# 468323_001_LED_DRV_ISO_2.net
KiCad netlist of a schematic drawn in Altium Designer
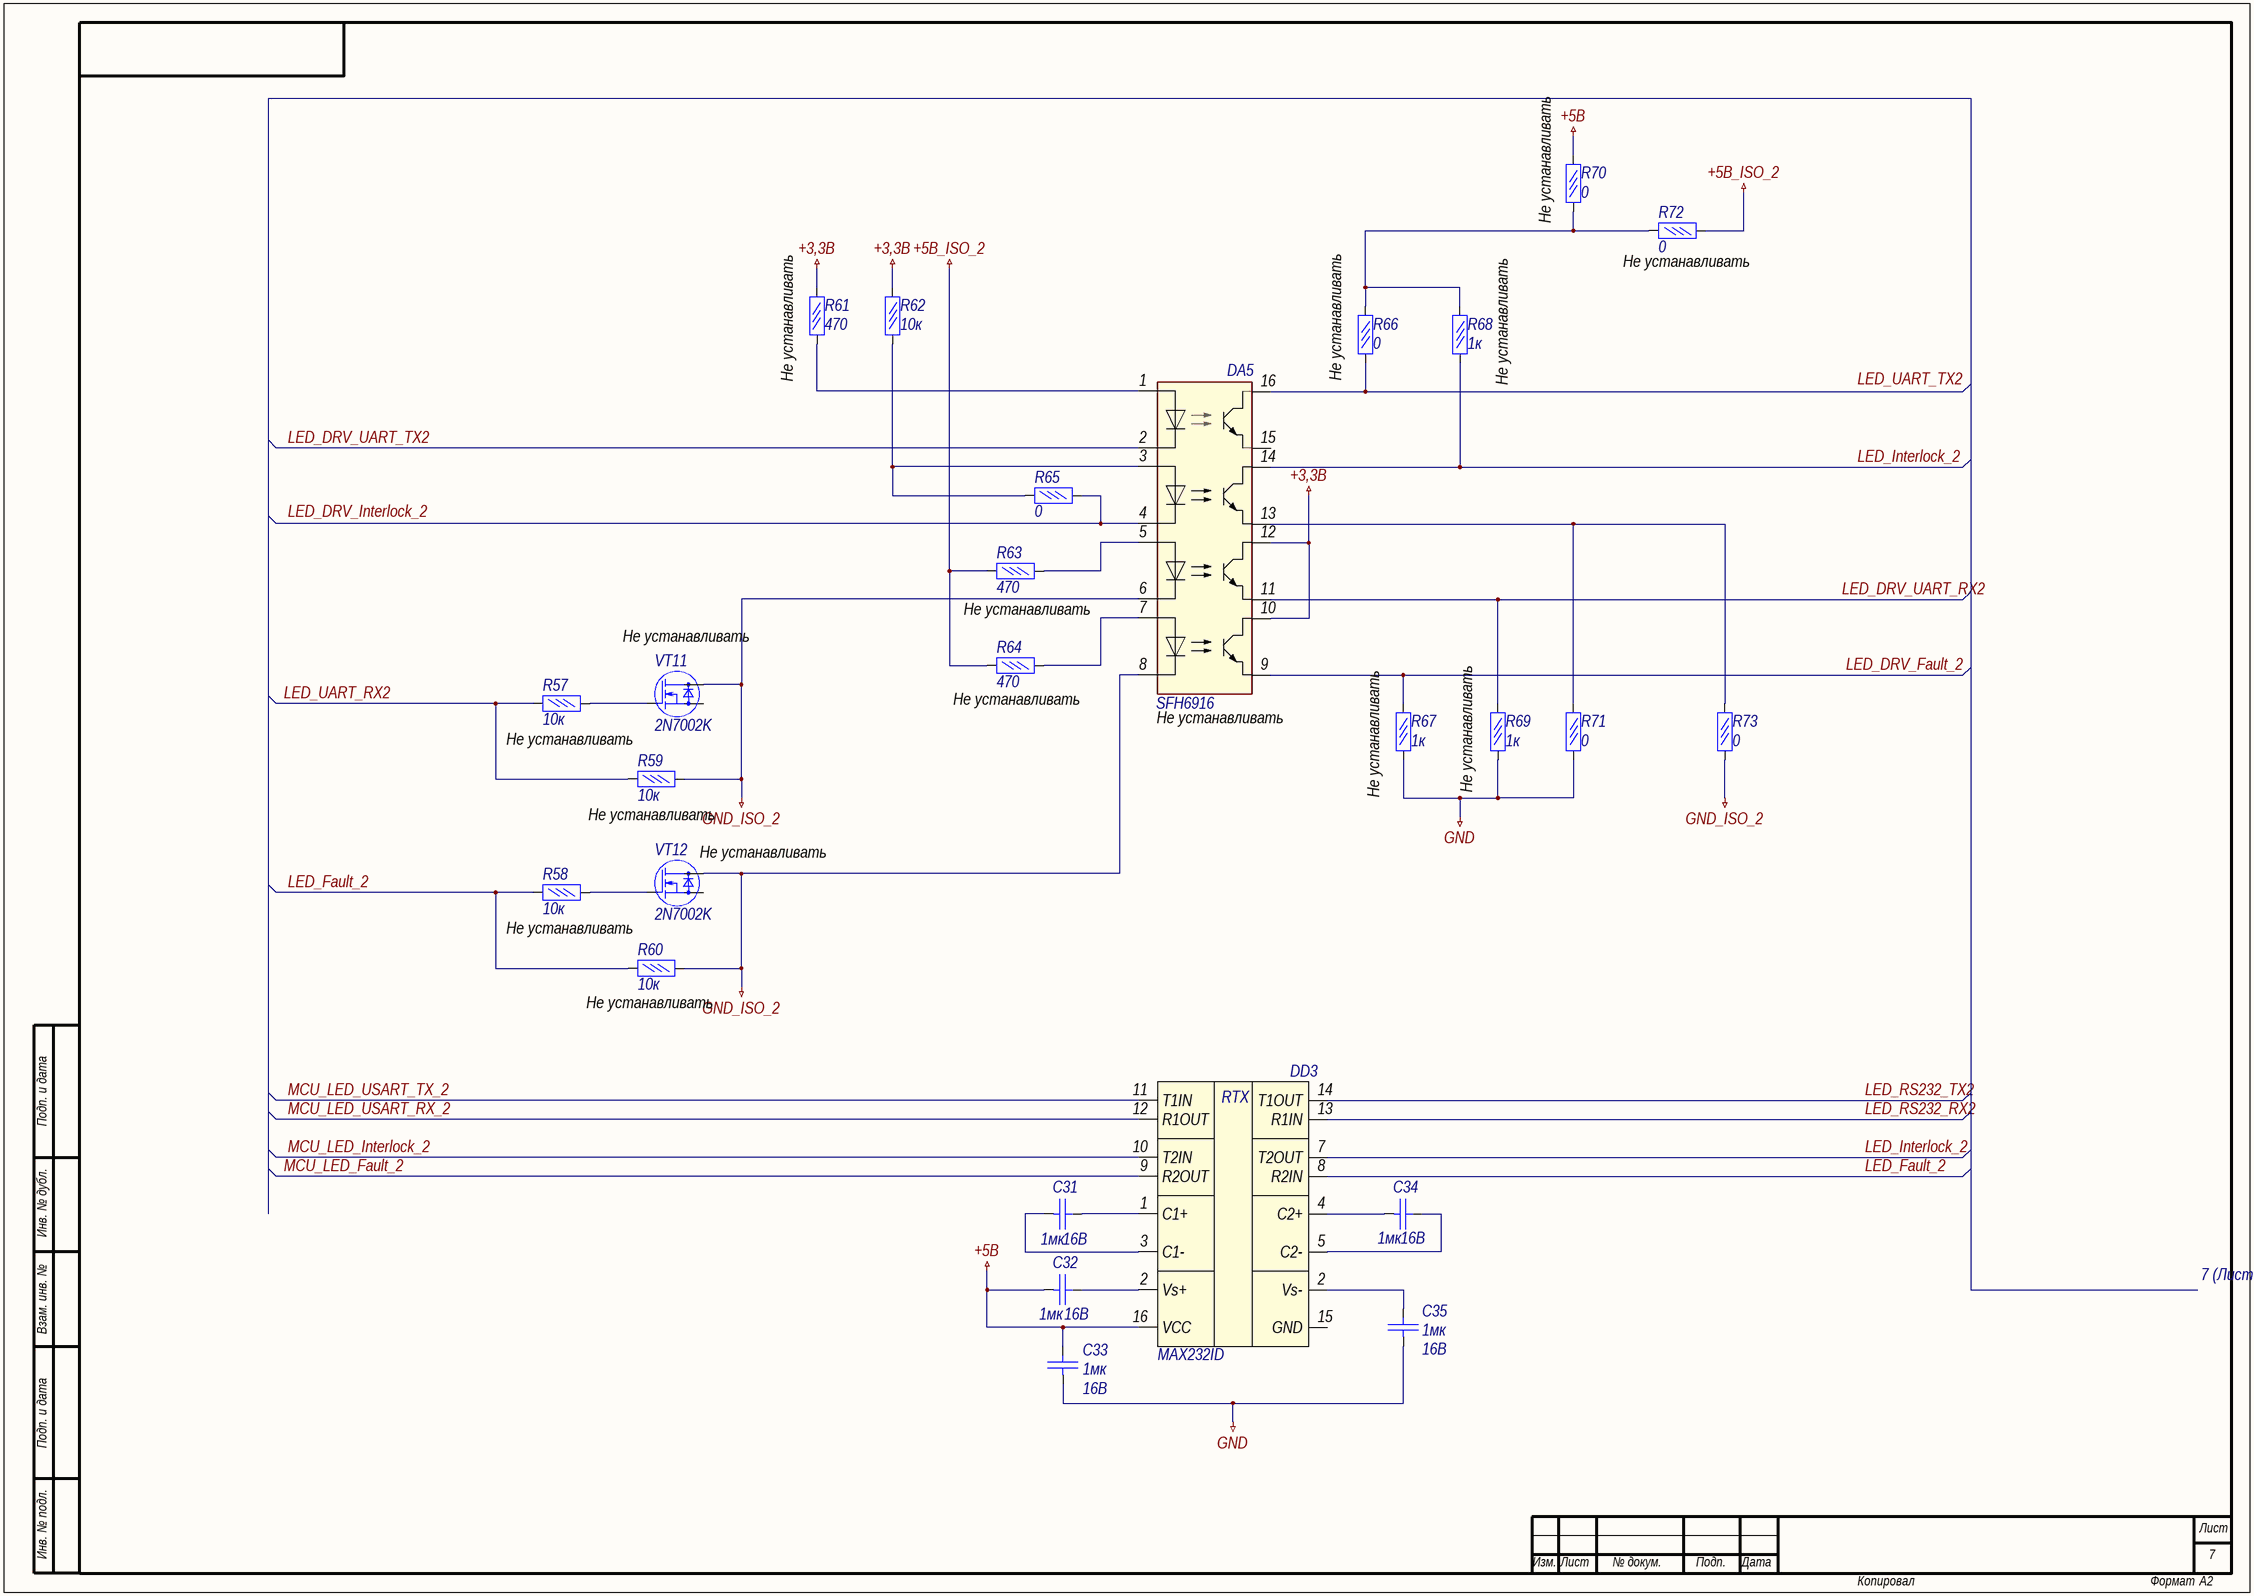
[diagram p0: РЕУН.468323.001_LED_DRV_ISO_2.SchDoc]

(export (version "E")
  (design (tool "Eeschema 10.0.6"))
  (components
    (comp (ref "C31")
      (value "1мк")
      (footprint "C0805_AA")
      (description "Конденсатор кер.")
      (fields (field (name "VOLTAGE") "16В"))
      (libsource (lib "Library_Diana") (part "Конденсатор кер."))
    )
    (comp (ref "C32")
      (value "1мк")
      (footprint "C0805_AA")
      (description "Конденсатор кер.")
      (fields (field (name "VOLTAGE") "16В"))
      (libsource (lib "Library_Diana") (part "Конденсатор кер."))
    )
    (comp (ref "C33")
      (value "1мк")
      (footprint "C0805_AA")
      (description "Конденсатор кер.")
      (fields (field (name "VOLTAGE") "16В"))
      (libsource (lib "Library_Diana") (part "Конденсатор кер."))
    )
    (comp (ref "C34")
      (value "1мк")
      (footprint "C0805_AA")
      (description "Конденсатор кер.")
      (fields (field (name "VOLTAGE") "16В"))
      (libsource (lib "Library_Diana") (part "Конденсатор кер."))
    )
    (comp (ref "C35")
      (value "1мк")
      (footprint "C0805_AA")
      (description "Конденсатор кер.")
      (fields (field (name "VOLTAGE") "16В"))
      (libsource (lib "Library_Diana") (part "Конденсатор кер."))
    )
    (comp (ref "DA5")
      (value "SFH6916")
      (description "Опторазвязка х4")
      (libsource (lib "Library_Diana") (part "OPTO-4"))
    )
    (comp (ref "DD3")
      (value "MAX232ID")
      (description "Dual EIA-232 Drivers/Receivers")
      (libsource (lib "Library_Diana") (part "MAX232ID"))
    )
    (comp (ref "R57")
      (value "10к")
      (footprint "R1206")
      (description "Резистор 0,05Вт")
      (libsource (lib "") (part "Резистор  0,05Вт_1"))
    )
    (comp (ref "R58")
      (value "10к")
      (footprint "R1206")
      (description "Резистор 0,05Вт")
      (libsource (lib "") (part "Резистор  0,05Вт_1"))
    )
    (comp (ref "R59")
      (value "10к")
      (footprint "R1206")
      (description "Резистор 0,05Вт")
      (libsource (lib "") (part "Резистор  0,05Вт_1"))
    )
    (comp (ref "R60")
      (value "10к")
      (footprint "R1206")
      (description "Резистор 0,05Вт")
      (libsource (lib "") (part "Резистор  0,05Вт_1"))
    )
    (comp (ref "R61")
      (value "470")
      (footprint "R1206")
      (description "Резистор 0,05Вт")
      (libsource (lib "") (part "Резистор  0,05Вт_2"))
    )
    (comp (ref "R62")
      (value "10к")
      (footprint "R1206")
      (description "Резистор 0,05Вт")
      (libsource (lib "Library_Diana") (part "Резистор  0,05Вт"))
    )
    (comp (ref "R63")
      (value "470")
      (footprint "R1206")
      (description "Резистор 0,05Вт")
      (libsource (lib "") (part "Резистор  0,05Вт_1"))
    )
    (comp (ref "R64")
      (value "470")
      (footprint "R1206")
      (description "Резистор 0,05Вт")
      (libsource (lib "") (part "Резистор  0,05Вт_1"))
    )
    (comp (ref "R65")
      (value "0")
      (footprint "R1206")
      (description "Резистор 0,05Вт")
      (libsource (lib "") (part "Резистор  0,05Вт_1"))
    )
    (comp (ref "R66")
      (value "0")
      (footprint "R1206")
      (description "Резистор 0,05Вт")
      (libsource (lib "Library_Diana") (part "Резистор  0,05Вт"))
    )
    (comp (ref "R67")
      (value "1к")
      (footprint "R1206")
      (description "Резистор 0,05Вт")
      (libsource (lib "Library_Diana") (part "Резистор  0,05Вт"))
    )
    (comp (ref "R68")
      (value "1к")
      (footprint "R1206")
      (description "Резистор 0,05Вт")
      (libsource (lib "Library_Diana") (part "Резистор  0,05Вт"))
    )
    (comp (ref "R69")
      (value "1к")
      (footprint "R1206")
      (description "Резистор 0,05Вт")
      (libsource (lib "Library_Diana") (part "Резистор  0,05Вт"))
    )
    (comp (ref "R70")
      (value "0")
      (footprint "R1206")
      (description "Резистор 0,05Вт")
      (libsource (lib "") (part "Резистор  0,05Вт_2"))
    )
    (comp (ref "R71")
      (value "0")
      (footprint "R1206")
      (description "Резистор 0,05Вт")
      (libsource (lib "Library_Diana") (part "Резистор  0,05Вт"))
    )
    (comp (ref "R72")
      (value "0")
      (footprint "R1206")
      (description "Резистор 0,05Вт")
      (libsource (lib "") (part "Резистор  0,05Вт_3"))
    )
    (comp (ref "R73")
      (value "0")
      (footprint "R1206")
      (description "Резистор 0,05Вт")
      (libsource (lib "Library_Diana") (part "Резистор  0,05Вт"))
    )
    (comp (ref "VT11")
      (value "2N7002K")
      (footprint "SOT:SOT23-3")
      (fields (field (name "NAME") "2N7002K"))
      (libsource (lib "Library_Diana") (part "mosfet-n"))
    )
    (comp (ref "VT12")
      (value "2N7002K")
      (footprint "SOT:SOT23-3")
      (fields (field (name "NAME") "2N7002K"))
      (libsource (lib "Library_Diana") (part "mosfet-n"))
    )
  )
  (nets
    (net (code "1") (name "+3,3В") (class "Default")
      (node (ref "DA5") (pin "10") (pintype "passive"))
      (node (ref "DA5") (pin "12") (pintype "passive"))
      (node (ref "R61") (pin "1") (pinfunction "1_1") (pintype "passive"))
      (node (ref "R62") (pin "2") (pinfunction "2_2") (pintype "passive"))
    )
    (net (code "2") (name "+5В") (class "Default")
      (node (ref "C32") (pin "2") (pinfunction "2_2") (pintype "passive"))
      (node (ref "C33") (pin "1") (pinfunction "1_1") (pintype "passive"))
      (node (ref "DD3") (pin "16") (pinfunction "VCC_16") (pintype "passive"))
      (node (ref "R70") (pin "1") (pinfunction "1_1") (pintype "passive"))
    )
    (net (code "3") (name "+5В_ISO_2") (class "Default")
      (node (ref "R63") (pin "1") (pinfunction "1_1") (pintype "passive"))
      (node (ref "R64") (pin "1") (pinfunction "1_1") (pintype "passive"))
      (node (ref "R72") (pin "1") (pinfunction "1_1") (pintype "passive"))
    )
    (net (code "4") (name "/LED_DRV_Fault_2") (class "Default")
      (node (ref "DA5") (pin "9") (pintype "passive"))
      (node (ref "R67") (pin "2") (pinfunction "2_2") (pintype "passive"))
    )
    (net (code "6") (name "/LED_DRV_UART_RX2") (class "Default")
      (node (ref "DA5") (pin "11") (pintype "passive"))
      (node (ref "R69") (pin "2") (pinfunction "2_2") (pintype "passive"))
    )
    (net (code "7") (name "/LED_DRV_UART_TX2") (class "Default")
      (node (ref "DA5") (pin "2") (pintype "passive"))
    )
    (net (code "8") (name "/LED_Fault_2") (class "Default")
      (node (ref "DD3") (pin "8") (pinfunction "R2IN_8") (pintype "passive"))
      (node (ref "R58") (pin "1") (pinfunction "1_1") (pintype "passive"))
      (node (ref "R60") (pin "1") (pinfunction "1_1") (pintype "passive"))
    )
    (net (code "9") (name "/LED_Interlock_2") (class "Default")
      (node (ref "DA5") (pin "14") (pintype "passive"))
      (node (ref "DD3") (pin "7") (pinfunction "T2OUT_7") (pintype "passive"))
      (node (ref "R68") (pin "1") (pinfunction "1_1") (pintype "passive"))
    )
    (net (code "10") (name "/LED_RS232_RX2") (class "Default")
      (node (ref "DD3") (pin "13") (pinfunction "R1IN_13") (pintype "passive"))
    )
    (net (code "11") (name "/LED_RS232_TX2") (class "Default")
      (node (ref "DD3") (pin "14") (pinfunction "T1OUT_14") (pintype "passive"))
    )
    (net (code "12") (name "/LED_UART_RX2") (class "Default")
      (node (ref "R57") (pin "1") (pinfunction "1_1") (pintype "passive"))
      (node (ref "R59") (pin "1") (pinfunction "1_1") (pintype "passive"))
    )
    (net (code "14") (name "/MCU_LED_Fault_2") (class "Default")
      (node (ref "DD3") (pin "9") (pinfunction "R2OUT_9") (pintype "passive"))
    )
    (net (code "15") (name "/MCU_LED_Interlock_2") (class "Default")
      (node (ref "DD3") (pin "10") (pinfunction "T2IN_10") (pintype "passive"))
    )
    (net (code "16") (name "/MCU_LED_USART_RX_2") (class "Default")
      (node (ref "DD3") (pin "12") (pinfunction "R1OUT_12") (pintype "passive"))
    )
    (net (code "17") (name "/MCU_LED_USART_TX_2") (class "Default")
      (node (ref "DD3") (pin "11") (pinfunction "T1IN_11") (pintype "passive"))
    )
    (net (code "18") (name "GND") (class "Default")
      (node (ref "C33") (pin "2") (pinfunction "2_2") (pintype "passive"))
      (node (ref "C35") (pin "2") (pinfunction "2_2") (pintype "passive"))
      (node (ref "R67") (pin "1") (pinfunction "1_1") (pintype "passive"))
      (node (ref "R69") (pin "1") (pinfunction "1_1") (pintype "passive"))
      (node (ref "R71") (pin "1") (pinfunction "1_1") (pintype "passive"))
    )
    (net (code "19") (name "GND_ISO_2") (class "Default")
      (node (ref "DA5") (pin "6") (pintype "passive"))
      (node (ref "DA5") (pin "8") (pintype "passive"))
      (node (ref "R59") (pin "2") (pinfunction "2_2") (pintype "passive"))
      (node (ref "R60") (pin "2") (pinfunction "2_2") (pintype "passive"))
      (node (ref "R73") (pin "1") (pinfunction "1_1") (pintype "passive"))
      (node (ref "VT11") (pin "3") (pinfunction "D_3") (pintype "passive"))
      (node (ref "VT12") (pin "3") (pinfunction "D_3") (pintype "passive"))
    )
    (net (code "20") (name "Net-(DA5-Pad1)") (class "Default")
      (node (ref "DA5") (pin "1") (pintype "passive"))
      (node (ref "R61") (pin "2") (pinfunction "2_2") (pintype "passive"))
    )
    (net (code "21") (name "Net-(DA5-Pad3)") (class "Default")
      (node (ref "DA5") (pin "3") (pintype "passive"))
      (node (ref "R62") (pin "1") (pinfunction "1_1") (pintype "passive"))
      (node (ref "R65") (pin "1") (pinfunction "1_1") (pintype "passive"))
    )
    (net (code "22") (name "Net-(DA5-Pad4)") (class "Default")
      (node (ref "DA5") (pin "4") (pintype "passive"))
      (node (ref "R65") (pin "2") (pinfunction "2_2") (pintype "passive"))
    )
    (net (code "23") (name "Net-(DA5-Pad5)") (class "Default")
      (node (ref "DA5") (pin "5") (pintype "passive"))
      (node (ref "R63") (pin "2") (pinfunction "2_2") (pintype "passive"))
    )
    (net (code "24") (name "Net-(DA5-Pad7)") (class "Default")
      (node (ref "DA5") (pin "7") (pintype "passive"))
      (node (ref "R64") (pin "2") (pinfunction "2_2") (pintype "passive"))
    )
    (net (code "25") (name "Net-(DA5-Pad13)") (class "Default")
      (node (ref "DA5") (pin "13") (pintype "passive"))
      (node (ref "R71") (pin "2") (pinfunction "2_2") (pintype "passive"))
      (node (ref "R73") (pin "2") (pinfunction "2_2") (pintype "passive"))
    )
    (net (code "26") (name "Net-(DA5-Pad16)") (class "Default")
      (node (ref "DA5") (pin "16") (pintype "passive"))
      (node (ref "R66") (pin "1") (pinfunction "1_1") (pintype "passive"))
    )
    (net (code "27") (name "Net-(DD3-C1+)") (class "Default")
      (node (ref "C31") (pin "1") (pinfunction "1_1") (pintype "passive"))
      (node (ref "DD3") (pin "1") (pinfunction "C1+_1") (pintype "passive"))
    )
    (net (code "28") (name "Net-(DD3-C1-)") (class "Default")
      (node (ref "C31") (pin "2") (pinfunction "2_2") (pintype "passive"))
      (node (ref "DD3") (pin "3") (pinfunction "C1-_3") (pintype "passive"))
    )
    (net (code "29") (name "Net-(DD3-C2+)") (class "Default")
      (node (ref "C34") (pin "2") (pinfunction "2_2") (pintype "passive"))
      (node (ref "DD3") (pin "4") (pinfunction "C2+_4") (pintype "passive"))
    )
    (net (code "30") (name "Net-(DD3-C2-)") (class "Default")
      (node (ref "C34") (pin "1") (pinfunction "1_1") (pintype "passive"))
      (node (ref "DD3") (pin "5") (pinfunction "C2-_5") (pintype "passive"))
    )
    (net (code "31") (name "Net-(DD3-Vs+)") (class "Default")
      (node (ref "C32") (pin "1") (pinfunction "1_1") (pintype "passive"))
      (node (ref "DD3") (pin "2") (pinfunction "Vs+_2") (pintype "passive"))
    )
    (net (code "32") (name "Net-(DD3-Vs-)") (class "Default")
      (node (ref "C35") (pin "1") (pinfunction "1_1") (pintype "passive"))
      (node (ref "DD3") (pin "2") (pinfunction "Vs-_2") (pintype "passive"))
    )
    (net (code "33") (name "Net-(R66-Pad2)") (class "Default")
      (node (ref "R66") (pin "2") (pinfunction "2_2") (pintype "passive"))
      (node (ref "R68") (pin "2") (pinfunction "2_2") (pintype "passive"))
      (node (ref "R70") (pin "2") (pinfunction "2_2") (pintype "passive"))
      (node (ref "R72") (pin "2") (pinfunction "2_2") (pintype "passive"))
    )
    (net (code "34") (name "Net-(VT11-G)") (class "Default")
      (node (ref "R57") (pin "2") (pinfunction "2_2") (pintype "passive"))
      (node (ref "VT11") (pin "1") (pinfunction "G_1") (pintype "passive"))
    )
    (net (code "35") (name "Net-(VT12-G)") (class "Default")
      (node (ref "R58") (pin "2") (pinfunction "2_2") (pintype "passive"))
      (node (ref "VT12") (pin "1") (pinfunction "G_1") (pintype "passive"))
    )
    (net (code "36") (name "unconnected-(DA5-Pad15)") (class "Default")
      (node (ref "DA5") (pin "15") (pintype "passive"))
    )
    (net (code "37") (name "unconnected-(DD3-GND-Pad15)") (class "Default")
      (node (ref "DD3") (pin "15") (pinfunction "GND_15") (pintype "passive"))
    )
    (net (code "38") (name "unconnected-(VT11-S-Pad2)") (class "Default")
      (node (ref "VT11") (pin "2") (pinfunction "S_2") (pintype "passive"))
    )
    (net (code "39") (name "unconnected-(VT12-S-Pad2)") (class "Default")
      (node (ref "VT12") (pin "2") (pinfunction "S_2") (pintype "passive"))
    )
  )
)
